# 03_MCU.net
KiCad netlist of a schematic drawn in Altium Designer
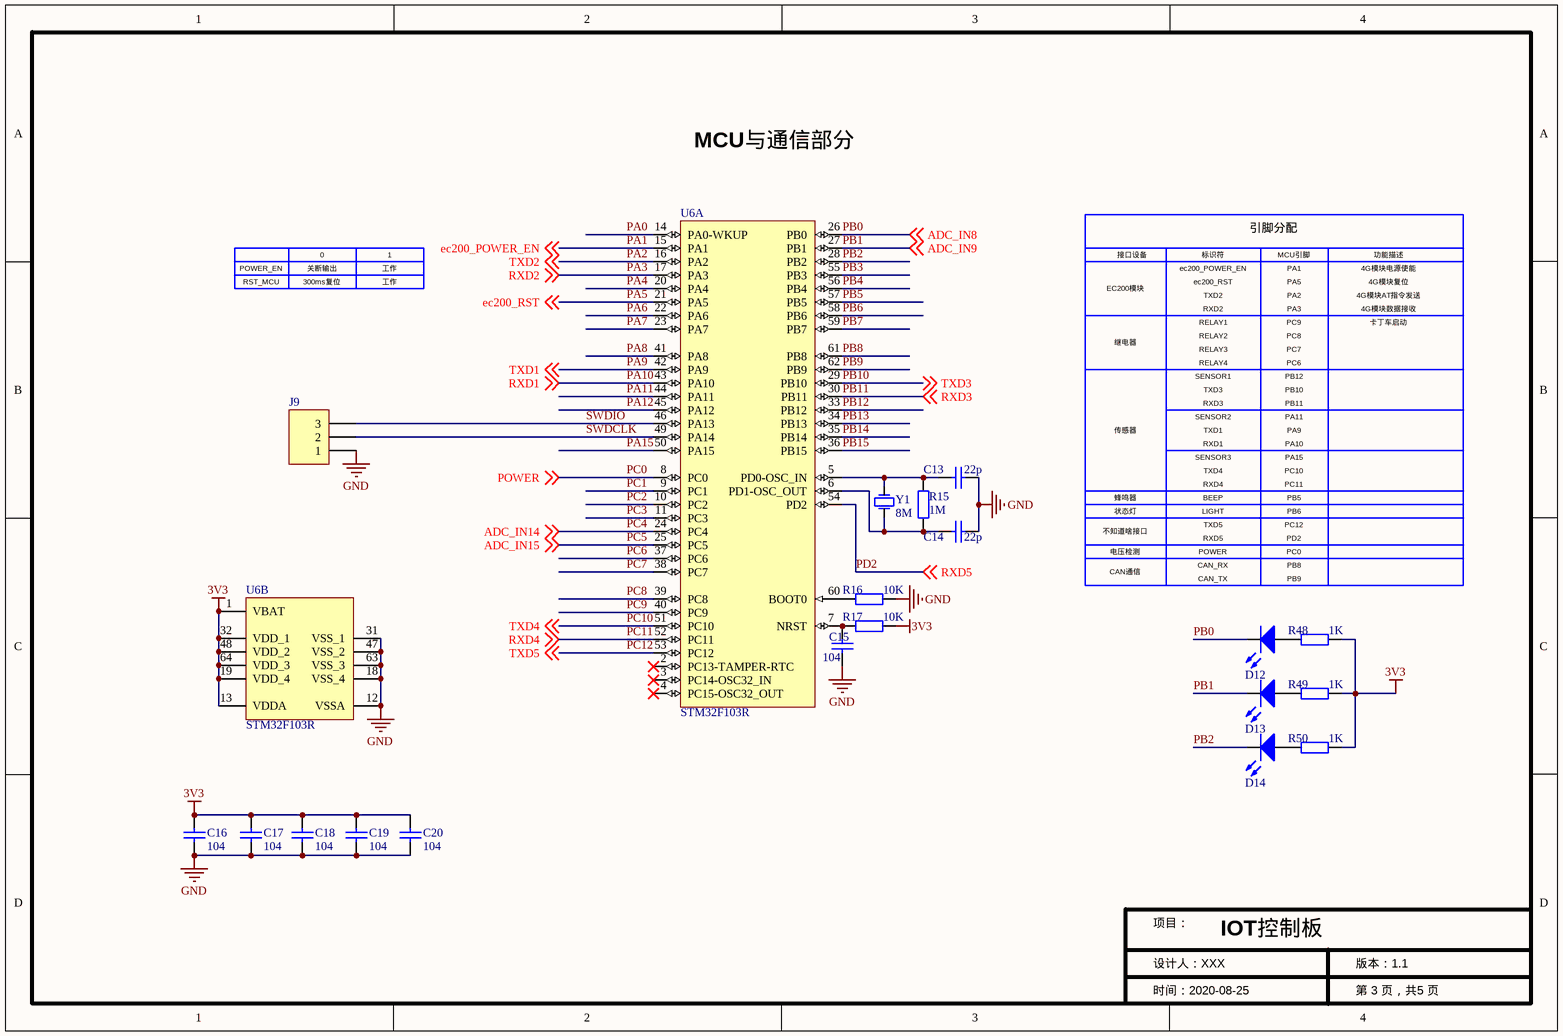
[diagram p0: 03_MCU部分.SchDoc]

(export (version "E")
  (design (tool "Eeschema 10.0.6"))
  (components
    (comp (ref "C13")
      (value "22p")
      (footprint "CAP-0603")
      (description "无极性电容")
      (fields (field (name "Comment") "Cap") (field (name "PUBLISHER") "Altium Limited"))
      (libsource (lib "Arrowy_Racing") (part "Cap"))
    )
    (comp (ref "C14")
      (value "22p")
      (footprint "CAP-0603")
      (description "无极性电容")
      (fields (field (name "Comment") "Cap") (field (name "PUBLISHER") "Altium Limited"))
      (libsource (lib "Arrowy_Racing") (part "Cap"))
    )
    (comp (ref "C15")
      (value "104")
      (footprint "CAP-0603")
      (description "无极性电容")
      (fields (field (name "Comment") "Cap") (field (name "PUBLISHER") "Altium Limited"))
      (libsource (lib "Arrowy_Racing") (part "Cap"))
    )
    (comp (ref "C16")
      (value "104")
      (footprint "CAP-0603")
      (description "无极性电容")
      (fields (field (name "Comment") "Cap") (field (name "PUBLISHER") "Altium Limited"))
      (libsource (lib "Arrowy_Racing") (part "Cap"))
    )
    (comp (ref "C17")
      (value "104")
      (footprint "CAP-0603")
      (description "无极性电容")
      (fields (field (name "Comment") "Cap") (field (name "PUBLISHER") "Altium Limited"))
      (libsource (lib "Arrowy_Racing") (part "Cap"))
    )
    (comp (ref "C18")
      (value "104")
      (footprint "CAP-0603")
      (description "无极性电容")
      (fields (field (name "Comment") "Cap") (field (name "PUBLISHER") "Altium Limited"))
      (libsource (lib "Arrowy_Racing") (part "Cap"))
    )
    (comp (ref "C19")
      (value "104")
      (footprint "CAP-0603")
      (description "无极性电容")
      (fields (field (name "Comment") "Cap") (field (name "PUBLISHER") "Altium Limited"))
      (libsource (lib "Arrowy_Racing") (part "Cap"))
    )
    (comp (ref "C20")
      (value "104")
      (footprint "CAP-0603")
      (description "无极性电容")
      (fields (field (name "Comment") "Cap") (field (name "PUBLISHER") "Altium Limited"))
      (libsource (lib "Arrowy_Racing") (part "Cap"))
    )
    (comp (ref "D12")
      (value "LED")
      (footprint "LED_0805")
      (description "发光二极管")
      (fields (field (name "PUBLISHER") "Altium Limited"))
      (libsource (lib "Arrowy_Racing") (part "LED"))
    )
    (comp (ref "D13")
      (value "LED")
      (footprint "LED_0805")
      (description "发光二极管")
      (fields (field (name "PUBLISHER") "Altium Limited"))
      (libsource (lib "Arrowy_Racing") (part "LED"))
    )
    (comp (ref "D14")
      (value "LED")
      (footprint "LED_0805")
      (description "发光二极管")
      (fields (field (name "PUBLISHER") "Altium Limited"))
      (libsource (lib "Arrowy_Racing") (part "LED"))
    )
    (comp (ref "J9")
      (value "Header3")
      (footprint "Header_3X1_2.54_排针")
      (description "接插件")
      (libsource (lib "Arrowy_Racing") (part "Header3"))
    )
    (comp (ref "R15")
      (value "1M")
      (footprint "0603")
      (description "贴片电阻")
      (fields (field (name "Comment") "Res") (field (name "PUBLISHER") "Altium Limited"))
      (libsource (lib "Arrowy_Racing") (part "Res"))
    )
    (comp (ref "R16")
      (value "10K")
      (footprint "0603")
      (description "贴片电阻")
      (fields (field (name "Comment") "Res") (field (name "PUBLISHER") "Altium Limited"))
      (libsource (lib "") (part "Res_1"))
    )
    (comp (ref "R17")
      (value "10K")
      (footprint "0603")
      (description "贴片电阻")
      (fields (field (name "Comment") "Res") (field (name "PUBLISHER") "Altium Limited"))
      (libsource (lib "") (part "Res_1"))
    )
    (comp (ref "R48")
      (value "1K")
      (footprint "0603")
      (description "贴片电阻")
      (fields (field (name "Comment") "Res") (field (name "PUBLISHER") "Altium Limited"))
      (libsource (lib "") (part "Res_1"))
    )
    (comp (ref "R49")
      (value "1K")
      (footprint "0603")
      (description "贴片电阻")
      (fields (field (name "Comment") "Res") (field (name "PUBLISHER") "Altium Limited"))
      (libsource (lib "") (part "Res_1"))
    )
    (comp (ref "R50")
      (value "1K")
      (footprint "0603")
      (description "贴片电阻")
      (fields (field (name "Comment") "Res") (field (name "PUBLISHER") "Altium Limited"))
      (libsource (lib "") (part "Res_1"))
    )
    (comp (ref "U6")
      (value "STM32F103R")
      (footprint "LQFP64")
      (description "STM32单片机64引脚")
      (fields (field (name "PARTNUMBER") "STM32F103RGT6"))
      (libsource (lib "Arrowy_Racing") (part "STM32F103R"))
    )
    (comp (ref "Y1")
      (value "8M")
      (footprint "X-SM49")
      (description "晶振")
      (fields (field (name "Comment") "XTAL") (field (name "PUBLISHER") "Altium Limited"))
      (libsource (lib "Arrowy_Racing") (part "XTAL"))
    )
  )
  (nets
    (net (code "1") (name "/PA0") (class "Default")
      (node (ref "U6") (pin "14") (pinfunction "PA0-WKUP_14") (pintype "bidirectional"))
    )
    (net (code "2") (name "/PA4") (class "Default")
      (node (ref "U6") (pin "20") (pinfunction "PA4_20") (pintype "bidirectional"))
    )
    (net (code "3") (name "/PA6") (class "Default")
      (node (ref "U6") (pin "22") (pinfunction "PA6_22") (pintype "bidirectional"))
    )
    (net (code "4") (name "/PA7") (class "Default")
      (node (ref "U6") (pin "23") (pinfunction "PA7_23") (pintype "bidirectional"))
    )
    (net (code "5") (name "/PA8") (class "Default")
      (node (ref "U6") (pin "41") (pinfunction "PA8_41") (pintype "bidirectional"))
    )
    (net (code "6") (name "/PA11") (class "Default")
      (node (ref "U6") (pin "44") (pinfunction "PA11_44") (pintype "bidirectional"))
    )
    (net (code "7") (name "/PA12") (class "Default")
      (node (ref "U6") (pin "45") (pinfunction "PA12_45") (pintype "bidirectional"))
    )
    (net (code "8") (name "/PA15") (class "Default")
      (node (ref "U6") (pin "50") (pinfunction "PA15_50") (pintype "bidirectional"))
    )
    (net (code "9") (name "/PB2") (class "Default")
      (node (ref "D14") (pin "2") (pinfunction "K_2") (pintype "passive"))
      (node (ref "U6") (pin "28") (pinfunction "PB2_28") (pintype "bidirectional"))
    )
    (net (code "10") (name "/PB3") (class "Default")
      (node (ref "U6") (pin "55") (pinfunction "PB3_55") (pintype "bidirectional"))
    )
    (net (code "11") (name "/PB4") (class "Default")
      (node (ref "U6") (pin "56") (pinfunction "PB4_56") (pintype "bidirectional"))
    )
    (net (code "12") (name "/PB5") (class "Default")
      (node (ref "U6") (pin "57") (pinfunction "PB5_57") (pintype "bidirectional"))
    )
    (net (code "13") (name "/PB6") (class "Default")
      (node (ref "U6") (pin "58") (pinfunction "PB6_58") (pintype "bidirectional"))
    )
    (net (code "14") (name "/PB7") (class "Default")
      (node (ref "U6") (pin "59") (pinfunction "PB7_59") (pintype "bidirectional"))
    )
    (net (code "15") (name "/PB8") (class "Default")
      (node (ref "U6") (pin "61") (pinfunction "PB8_61") (pintype "bidirectional"))
    )
    (net (code "16") (name "/PB9") (class "Default")
      (node (ref "U6") (pin "62") (pinfunction "PB9_62") (pintype "bidirectional"))
    )
    (net (code "17") (name "/PB12") (class "Default")
      (node (ref "U6") (pin "33") (pinfunction "PB12_33") (pintype "bidirectional"))
    )
    (net (code "18") (name "/PB13") (class "Default")
      (node (ref "U6") (pin "34") (pinfunction "PB13_34") (pintype "bidirectional"))
    )
    (net (code "19") (name "/PB14") (class "Default")
      (node (ref "U6") (pin "35") (pinfunction "PB14_35") (pintype "bidirectional"))
    )
    (net (code "20") (name "/PB15") (class "Default")
      (node (ref "U6") (pin "36") (pinfunction "PB15_36") (pintype "bidirectional"))
    )
    (net (code "21") (name "/PC1") (class "Default")
      (node (ref "U6") (pin "9") (pinfunction "PC1_9") (pintype "bidirectional"))
    )
    (net (code "22") (name "/PC2") (class "Default")
      (node (ref "U6") (pin "10") (pinfunction "PC2_10") (pintype "bidirectional"))
    )
    (net (code "23") (name "/PC3") (class "Default")
      (node (ref "U6") (pin "11") (pinfunction "PC3_11") (pintype "bidirectional"))
    )
    (net (code "24") (name "/PC6") (class "Default")
      (node (ref "U6") (pin "37") (pinfunction "PC6_37") (pintype "bidirectional"))
    )
    (net (code "25") (name "/PC7") (class "Default")
      (node (ref "U6") (pin "38") (pinfunction "PC7_38") (pintype "bidirectional"))
    )
    (net (code "26") (name "/PC8") (class "Default")
      (node (ref "U6") (pin "39") (pinfunction "PC8_39") (pintype "bidirectional"))
    )
    (net (code "27") (name "/PC9") (class "Default")
      (node (ref "U6") (pin "40") (pinfunction "PC9_40") (pintype "bidirectional"))
    )
    (net (code "28") (name "/SWDCLK") (class "Default")
      (node (ref "J9") (pin "2") (pinfunction "2_2") (pintype "passive"))
      (node (ref "U6") (pin "49") (pinfunction "PA14_49") (pintype "bidirectional"))
    )
    (net (code "29") (name "/SWDIO") (class "Default")
      (node (ref "J9") (pin "3") (pinfunction "3_3") (pintype "passive"))
      (node (ref "U6") (pin "46") (pinfunction "PA13_46") (pintype "bidirectional"))
    )
    (net (code "30") (name "3V3") (class "Default")
      (node (ref "C16") (pin "2") (pinfunction "2_2") (pintype "passive"))
      (node (ref "C17") (pin "2") (pinfunction "2_2") (pintype "passive"))
      (node (ref "C18") (pin "2") (pinfunction "2_2") (pintype "passive"))
      (node (ref "C19") (pin "2") (pinfunction "2_2") (pintype "passive"))
      (node (ref "C20") (pin "2") (pinfunction "2_2") (pintype "passive"))
      (node (ref "R17") (pin "1") (pinfunction "1_1") (pintype "passive"))
      (node (ref "R48") (pin "1") (pinfunction "1_1") (pintype "passive"))
      (node (ref "R49") (pin "1") (pinfunction "1_1") (pintype "passive"))
      (node (ref "R50") (pin "1") (pinfunction "1_1") (pintype "passive"))
      (node (ref "U6") (pin "1") (pinfunction "VBAT_1") (pintype "power_in"))
      (node (ref "U6") (pin "13") (pinfunction "VDDA_13") (pintype "power_in"))
      (node (ref "U6") (pin "19") (pinfunction "VDD_4_19") (pintype "power_in"))
      (node (ref "U6") (pin "32") (pinfunction "VDD_1_32") (pintype "power_in"))
      (node (ref "U6") (pin "48") (pinfunction "VDD_2_48") (pintype "power_in"))
      (node (ref "U6") (pin "64") (pinfunction "VDD_3_64") (pintype "power_in"))
    )
    (net (code "31") (name "ADC_IN8") (class "Default")
      (node (ref "D12") (pin "2") (pinfunction "K_2") (pintype "passive"))
      (node (ref "U6") (pin "26") (pinfunction "PB0_26") (pintype "bidirectional"))
    )
    (net (code "32") (name "ADC_IN9") (class "Default")
      (node (ref "D13") (pin "2") (pinfunction "K_2") (pintype "passive"))
      (node (ref "U6") (pin "27") (pinfunction "PB1_27") (pintype "bidirectional"))
    )
    (net (code "33") (name "ADC_IN14") (class "Default")
      (node (ref "U6") (pin "24") (pinfunction "PC4_24") (pintype "bidirectional"))
    )
    (net (code "34") (name "ADC_IN15") (class "Default")
      (node (ref "U6") (pin "25") (pinfunction "PC5_25") (pintype "bidirectional"))
    )
    (net (code "35") (name "GND") (class "Default")
      (node (ref "C13") (pin "1") (pinfunction "1_1") (pintype "passive"))
      (node (ref "C14") (pin "1") (pinfunction "1_1") (pintype "passive"))
      (node (ref "C15") (pin "1") (pinfunction "1_1") (pintype "passive"))
      (node (ref "C16") (pin "1") (pinfunction "1_1") (pintype "passive"))
      (node (ref "C17") (pin "1") (pinfunction "1_1") (pintype "passive"))
      (node (ref "C18") (pin "1") (pinfunction "1_1") (pintype "passive"))
      (node (ref "C19") (pin "1") (pinfunction "1_1") (pintype "passive"))
      (node (ref "C20") (pin "1") (pinfunction "1_1") (pintype "passive"))
      (node (ref "J9") (pin "1") (pinfunction "1_1") (pintype "passive"))
      (node (ref "R16") (pin "1") (pinfunction "1_1") (pintype "passive"))
      (node (ref "U6") (pin "12") (pinfunction "VSSA_12") (pintype "power_in"))
      (node (ref "U6") (pin "18") (pinfunction "VSS_4_18") (pintype "power_in"))
      (node (ref "U6") (pin "31") (pinfunction "VSS_1_31") (pintype "power_in"))
      (node (ref "U6") (pin "47") (pinfunction "VSS_2_47") (pintype "power_in"))
      (node (ref "U6") (pin "63") (pinfunction "VSS_3_63") (pintype "power_in"))
    )
    (net (code "36") (name "Net-(D12-A)") (class "Default")
      (node (ref "D12") (pin "1") (pinfunction "A_1") (pintype "passive"))
      (node (ref "R48") (pin "2") (pinfunction "2_2") (pintype "passive"))
    )
    (net (code "37") (name "Net-(D13-A)") (class "Default")
      (node (ref "D13") (pin "1") (pinfunction "A_1") (pintype "passive"))
      (node (ref "R49") (pin "2") (pinfunction "2_2") (pintype "passive"))
    )
    (net (code "38") (name "Net-(D14-A)") (class "Default")
      (node (ref "D14") (pin "1") (pinfunction "A_1") (pintype "passive"))
      (node (ref "R50") (pin "2") (pinfunction "2_2") (pintype "passive"))
    )
    (net (code "39") (name "Net-(U6A-BOOT0)") (class "Default")
      (node (ref "R16") (pin "2") (pinfunction "2_2") (pintype "passive"))
      (node (ref "U6") (pin "60") (pinfunction "BOOT0_60") (pintype "input"))
    )
    (net (code "40") (name "Net-(U6A-NRST)") (class "Default")
      (node (ref "C15") (pin "2") (pinfunction "2_2") (pintype "passive"))
      (node (ref "R17") (pin "2") (pinfunction "2_2") (pintype "passive"))
      (node (ref "U6") (pin "7") (pinfunction "NRST_7") (pintype "bidirectional"))
    )
    (net (code "41") (name "Net-(U6A-PD0-OSC_IN)") (class "Default")
      (node (ref "C13") (pin "2") (pinfunction "2_2") (pintype "passive"))
      (node (ref "R15") (pin "2") (pinfunction "2_2") (pintype "passive"))
      (node (ref "U6") (pin "5") (pinfunction "PD0-OSC_IN_5") (pintype "bidirectional"))
      (node (ref "Y1") (pin "2") (pinfunction "2_2") (pintype "passive"))
    )
    (net (code "42") (name "Net-(U6A-PD1-OSC_OUT)") (class "Default")
      (node (ref "C14") (pin "2") (pinfunction "2_2") (pintype "passive"))
      (node (ref "R15") (pin "1") (pinfunction "1_1") (pintype "passive"))
      (node (ref "U6") (pin "6") (pinfunction "PD1-OSC_OUT_6") (pintype "bidirectional"))
      (node (ref "Y1") (pin "1") (pinfunction "1_1") (pintype "passive"))
    )
    (net (code "43") (name "POWER") (class "Default")
      (node (ref "U6") (pin "8") (pinfunction "PC0_8") (pintype "bidirectional"))
    )
    (net (code "44") (name "RXD1") (class "Default")
      (node (ref "U6") (pin "43") (pinfunction "PA10_43") (pintype "bidirectional"))
    )
    (net (code "45") (name "RXD2") (class "Default")
      (node (ref "U6") (pin "17") (pinfunction "PA3_17") (pintype "bidirectional"))
    )
    (net (code "46") (name "RXD3") (class "Default")
      (node (ref "U6") (pin "30") (pinfunction "PB11_30") (pintype "bidirectional"))
    )
    (net (code "47") (name "RXD4") (class "Default")
      (node (ref "U6") (pin "52") (pinfunction "PC11_52") (pintype "bidirectional"))
    )
    (net (code "48") (name "RXD5") (class "Default")
      (node (ref "U6") (pin "54") (pinfunction "PD2_54") (pintype "bidirectional"))
    )
    (net (code "49") (name "TXD1") (class "Default")
      (node (ref "U6") (pin "42") (pinfunction "PA9_42") (pintype "bidirectional"))
    )
    (net (code "50") (name "TXD2") (class "Default")
      (node (ref "U6") (pin "16") (pinfunction "PA2_16") (pintype "bidirectional"))
    )
    (net (code "51") (name "TXD3") (class "Default")
      (node (ref "U6") (pin "29") (pinfunction "PB10_29") (pintype "bidirectional"))
    )
    (net (code "52") (name "TXD4") (class "Default")
      (node (ref "U6") (pin "51") (pinfunction "PC10_51") (pintype "bidirectional"))
    )
    (net (code "53") (name "TXD5") (class "Default")
      (node (ref "U6") (pin "53") (pinfunction "PC12_53") (pintype "bidirectional"))
    )
    (net (code "54") (name "ec200_POWER_EN") (class "Default")
      (node (ref "U6") (pin "15") (pinfunction "PA1_15") (pintype "bidirectional"))
    )
    (net (code "55") (name "ec200_RST") (class "Default")
      (node (ref "U6") (pin "21") (pinfunction "PA5_21") (pintype "bidirectional"))
    )
    (net (code "56") (name "unconnected-(U6A-PC13-TAMPER-RTC-Pad2)") (class "Default")
      (node (ref "U6") (pin "2") (pinfunction "PC13-TAMPER-RTC_2") (pintype "bidirectional+no_connect"))
    )
    (net (code "57") (name "unconnected-(U6A-PC14-OSC32_IN-Pad3)") (class "Default")
      (node (ref "U6") (pin "3") (pinfunction "PC14-OSC32_IN_3") (pintype "bidirectional+no_connect"))
    )
    (net (code "58") (name "unconnected-(U6A-PC15-OSC32_OUT-Pad4)") (class "Default")
      (node (ref "U6") (pin "4") (pinfunction "PC15-OSC32_OUT_4") (pintype "bidirectional+no_connect"))
    )
  )
)
